# 4x1button_msp430_v5.net
KiCad netlist of a schematic drawn in EAGLE
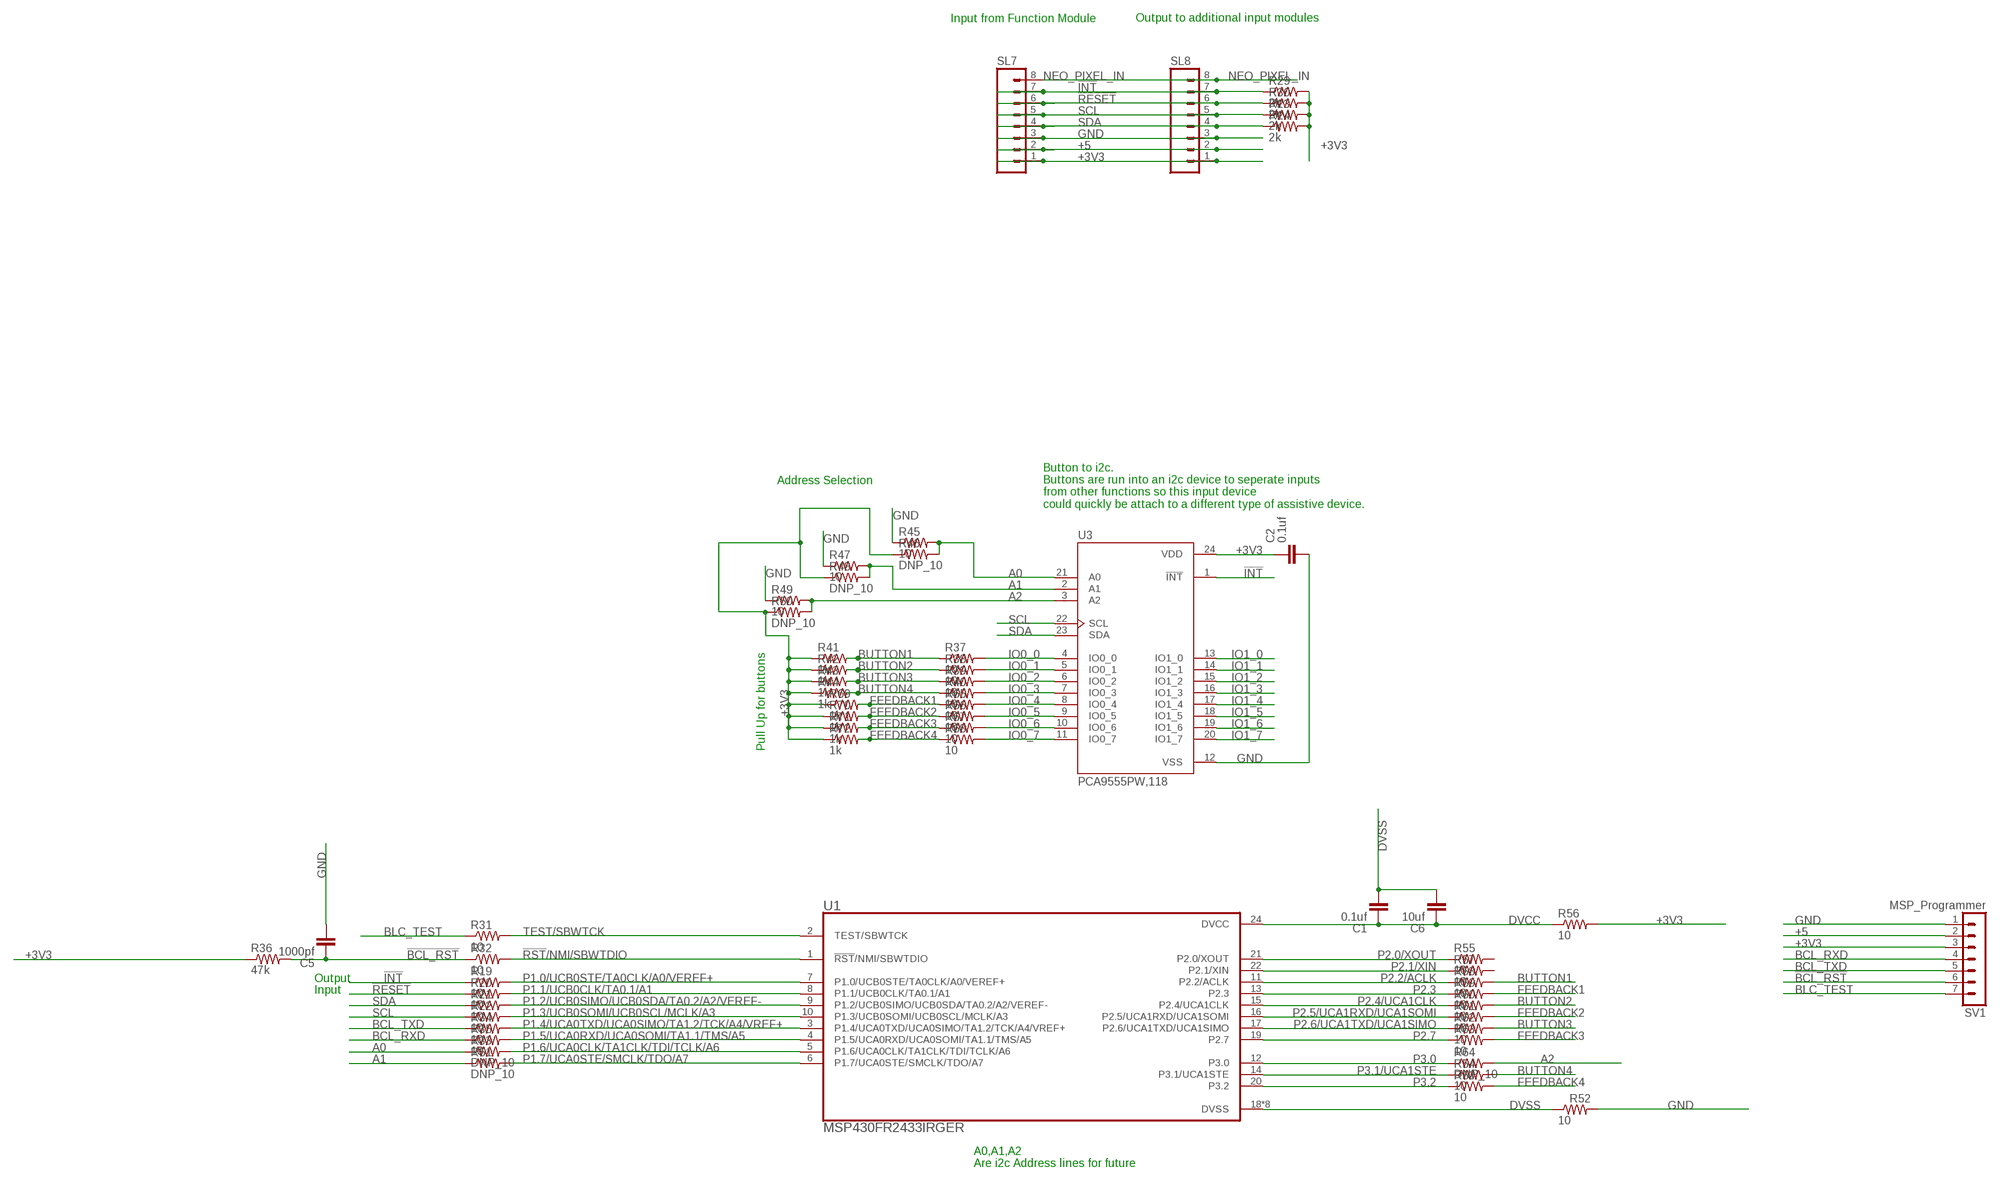
[diagram p0: schematic, sheet 1]
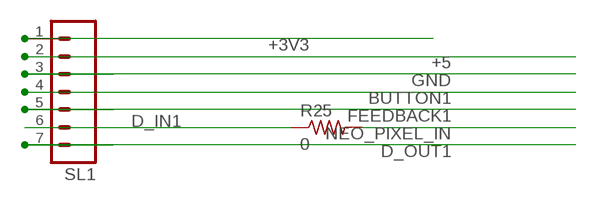
[diagram p1: schematic, sheet 2]
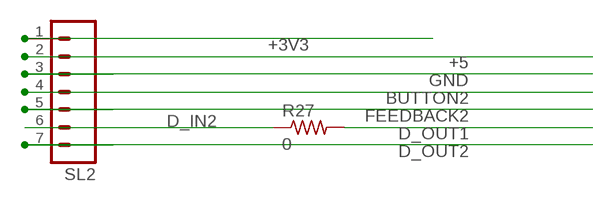
[diagram p2: schematic, sheet 3]
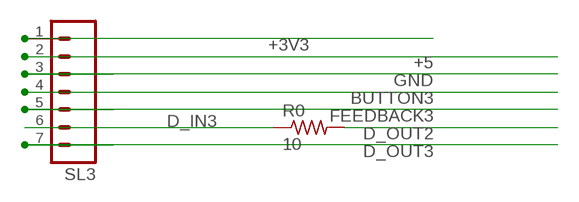
[diagram p3: schematic, sheet 4]
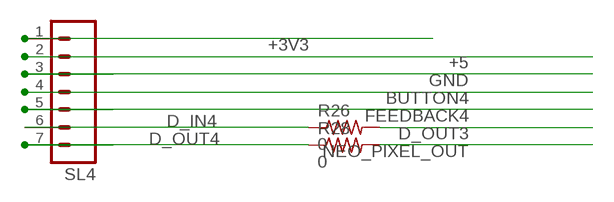
[diagram p4: schematic, sheet 5]
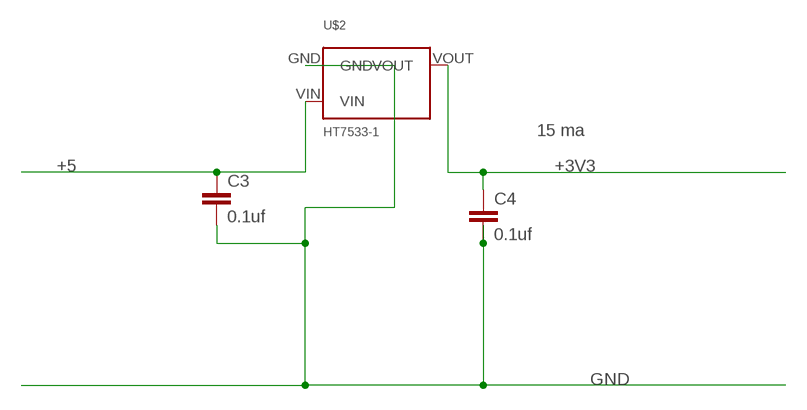
[diagram p5: schematic, sheet 6]

(export (version "E")
  (design (tool "Eeschema 10.0.6"))
  (components
    (comp (ref "R25")
      (value "0")
      (footprint "eagle-import:R0805")
      (libsource (lib "eagle-import") (part "R-US_R0805"))
    )
    (comp (ref "SL1")
      (value "MA07")
      (footprint "eagle-import:07PA")
      (libsource (lib "eagle-import") (part "MA07"))
    )
    (comp (ref "C3")
      (value "0.1uf")
      (footprint "eagle-import:C0805")
      (libsource (lib "eagle-import") (part "C-EUC0805"))
    )
    (comp (ref "C4")
      (value "0.1uf")
      (footprint "eagle-import:C0805")
      (libsource (lib "eagle-import") (part "C-EUC0805"))
    )
    (comp (ref "U$2")
      (value "HT7533-1")
      (footprint "eagle-import:HT7750-1")
      (libsource (lib "eagle-import") (part "HT7550-1"))
    )
    (comp (ref "C1")
      (value "0.1uf")
      (footprint "eagle-import:CAPC2012X110")
      (libsource (lib "eagle-import") (part "CCHIP-0805(2012-METRIC)_"))
    )
    (comp (ref "C2")
      (value "0.1uf")
      (footprint "eagle-import:CAPC2012X110")
      (libsource (lib "eagle-import") (part "CCHIP-0805(2012-METRIC)_"))
    )
    (comp (ref "C5")
      (value "1000pf")
      (footprint "eagle-import:CAPC2012X110")
      (libsource (lib "eagle-import") (part "CCHIP-0805(2012-METRIC)_"))
    )
    (comp (ref "C6")
      (value "10uf")
      (footprint "eagle-import:CAPC2012X110")
      (libsource (lib "eagle-import") (part "CCHIP-0805(2012-METRIC)_"))
    )
    (comp (ref "R19")
      (value "10")
      (footprint "eagle-import:R0805")
      (libsource (lib "eagle-import") (part "R-US_R0805"))
    )
    (comp (ref "R20")
      (value "10")
      (footprint "eagle-import:R0805")
      (libsource (lib "eagle-import") (part "R-US_R0805"))
    )
    (comp (ref "R21")
      (value "10")
      (footprint "eagle-import:R0805")
      (libsource (lib "eagle-import") (part "R-US_R0805"))
    )
    (comp (ref "R22")
      (value "10")
      (footprint "eagle-import:R0805")
      (libsource (lib "eagle-import") (part "R-US_R0805"))
    )
    (comp (ref "R23")
      (value "2k")
      (footprint "eagle-import:R0805")
      (libsource (lib "eagle-import") (part "R-US_R0805"))
    )
    (comp (ref "R24")
      (value "2k")
      (footprint "eagle-import:R0805")
      (libsource (lib "eagle-import") (part "R-US_R0805"))
    )
    (comp (ref "R29")
      (value "2k")
      (footprint "eagle-import:R0805")
      (libsource (lib "eagle-import") (part "R-US_R0805"))
    )
    (comp (ref "R30")
      (value "2k")
      (footprint "eagle-import:R0805")
      (libsource (lib "eagle-import") (part "R-US_R0805"))
    )
    (comp (ref "R31")
      (value "10")
      (footprint "eagle-import:R0805")
      (libsource (lib "eagle-import") (part "R-US_R0805"))
    )
    (comp (ref "R32")
      (value "10")
      (footprint "eagle-import:R0805")
      (libsource (lib "eagle-import") (part "R-US_R0805"))
    )
    (comp (ref "R33")
      (value "DNP_10")
      (footprint "eagle-import:R0805")
      (libsource (lib "eagle-import") (part "R-US_R0805"))
    )
    (comp (ref "R34")
      (value "10")
      (footprint "eagle-import:R0805")
      (libsource (lib "eagle-import") (part "R-US_R0805"))
    )
    (comp (ref "R35")
      (value "10")
      (footprint "eagle-import:R0805")
      (libsource (lib "eagle-import") (part "R-US_R0805"))
    )
    (comp (ref "R36")
      (value "47k")
      (footprint "eagle-import:R0805")
      (libsource (lib "eagle-import") (part "R-US_R0805"))
    )
    (comp (ref "R37")
      (value "10")
      (footprint "eagle-import:R0805")
      (libsource (lib "eagle-import") (part "R-US_R0805"))
    )
    (comp (ref "R38")
      (value "10")
      (footprint "eagle-import:R0805")
      (libsource (lib "eagle-import") (part "R-US_R0805"))
    )
    (comp (ref "R39")
      (value "10")
      (footprint "eagle-import:R0805")
      (libsource (lib "eagle-import") (part "R-US_R0805"))
    )
    (comp (ref "R40")
      (value "10")
      (footprint "eagle-import:R0805")
      (libsource (lib "eagle-import") (part "R-US_R0805"))
    )
    (comp (ref "R41")
      (value "1k")
      (footprint "eagle-import:R0805")
      (libsource (lib "eagle-import") (part "R-US_R0805"))
    )
    (comp (ref "R42")
      (value "1k")
      (footprint "eagle-import:R0805")
      (libsource (lib "eagle-import") (part "R-US_R0805"))
    )
    (comp (ref "R43")
      (value "1k")
      (footprint "eagle-import:R0805")
      (libsource (lib "eagle-import") (part "R-US_R0805"))
    )
    (comp (ref "R44")
      (value "1k")
      (footprint "eagle-import:R0805")
      (libsource (lib "eagle-import") (part "R-US_R0805"))
    )
    (comp (ref "R45")
      (value "10")
      (footprint "eagle-import:R0805")
      (libsource (lib "eagle-import") (part "R-US_R0805"))
    )
    (comp (ref "R46")
      (value "DNP_10")
      (footprint "eagle-import:R0805")
      (libsource (lib "eagle-import") (part "R-US_R0805"))
    )
    (comp (ref "R47")
      (value "10")
      (footprint "eagle-import:R0805")
      (libsource (lib "eagle-import") (part "R-US_R0805"))
    )
    (comp (ref "R48")
      (value "DNP_10")
      (footprint "eagle-import:R0805")
      (libsource (lib "eagle-import") (part "R-US_R0805"))
    )
    (comp (ref "R49")
      (value "10")
      (footprint "eagle-import:R0805")
      (libsource (lib "eagle-import") (part "R-US_R0805"))
    )
    (comp (ref "R50")
      (value "DNP_10")
      (footprint "eagle-import:R0805")
      (libsource (lib "eagle-import") (part "R-US_R0805"))
    )
    (comp (ref "R51")
      (value "DNP_10")
      (footprint "eagle-import:R0805")
      (libsource (lib "eagle-import") (part "R-US_R0805"))
    )
    (comp (ref "R52")
      (value "10")
      (footprint "eagle-import:R0805")
      (libsource (lib "eagle-import") (part "R-US_R0805"))
    )
    (comp (ref "R53")
      (value "10")
      (footprint "eagle-import:R0805")
      (libsource (lib "eagle-import") (part "R-US_R0805"))
    )
    (comp (ref "R54")
      (value "10")
      (footprint "eagle-import:R0805")
      (libsource (lib "eagle-import") (part "R-US_R0805"))
    )
    (comp (ref "R55")
      (value "10")
      (footprint "eagle-import:R0805")
      (libsource (lib "eagle-import") (part "R-US_R0805"))
    )
    (comp (ref "R56")
      (value "10")
      (footprint "eagle-import:R0805")
      (libsource (lib "eagle-import") (part "R-US_R0805"))
    )
    (comp (ref "R57")
      (value "10")
      (footprint "eagle-import:R0805")
      (libsource (lib "eagle-import") (part "R-US_R0805"))
    )
    (comp (ref "R58")
      (value "10")
      (footprint "eagle-import:R0805")
      (libsource (lib "eagle-import") (part "R-US_R0805"))
    )
    (comp (ref "R59")
      (value "10")
      (footprint "eagle-import:R0805")
      (libsource (lib "eagle-import") (part "R-US_R0805"))
    )
    (comp (ref "R60")
      (value "10")
      (footprint "eagle-import:R0805")
      (libsource (lib "eagle-import") (part "R-US_R0805"))
    )
    (comp (ref "R61")
      (value "10")
      (footprint "eagle-import:R0805")
      (libsource (lib "eagle-import") (part "R-US_R0805"))
    )
    (comp (ref "R62")
      (value "10")
      (footprint "eagle-import:R0805")
      (libsource (lib "eagle-import") (part "R-US_R0805"))
    )
    (comp (ref "R63")
      (value "10")
      (footprint "eagle-import:R0805")
      (libsource (lib "eagle-import") (part "R-US_R0805"))
    )
    (comp (ref "R64")
      (value "DNP_10")
      (footprint "eagle-import:R0805")
      (libsource (lib "eagle-import") (part "R-US_R0805"))
    )
    (comp (ref "R65")
      (value "10")
      (footprint "eagle-import:R0805")
      (libsource (lib "eagle-import") (part "R-US_R0805"))
    )
    (comp (ref "R66")
      (value "10")
      (footprint "eagle-import:R0805")
      (libsource (lib "eagle-import") (part "R-US_R0805"))
    )
    (comp (ref "R67")
      (value "10")
      (footprint "eagle-import:R0805")
      (libsource (lib "eagle-import") (part "R-US_R0805"))
    )
    (comp (ref "R68")
      (value "10")
      (footprint "eagle-import:R0805")
      (libsource (lib "eagle-import") (part "R-US_R0805"))
    )
    (comp (ref "R69")
      (value "1k")
      (footprint "eagle-import:R0805")
      (libsource (lib "eagle-import") (part "R-US_R0805"))
    )
    (comp (ref "R70")
      (value "1k")
      (footprint "eagle-import:R0805")
      (libsource (lib "eagle-import") (part "R-US_R0805"))
    )
    (comp (ref "R71")
      (value "1k")
      (footprint "eagle-import:R0805")
      (libsource (lib "eagle-import") (part "R-US_R0805"))
    )
    (comp (ref "R72")
      (value "1k")
      (footprint "eagle-import:R0805")
      (libsource (lib "eagle-import") (part "R-US_R0805"))
    )
    (comp (ref "SL7")
      (value "MA08")
      (footprint "eagle-import:08PA")
      (libsource (lib "eagle-import") (part "MA08"))
    )
    (comp (ref "SL8")
      (value "MA08")
      (footprint "eagle-import:08PA")
      (libsource (lib "eagle-import") (part "MA08"))
    )
    (comp (ref "SV1")
      (value "MSP_Programmer")
      (footprint "eagle-import:MA07-1")
      (libsource (lib "eagle-import") (part "MA07-1"))
    )
    (comp (ref "U1")
      (value "MSP430FR2433IRGER")
      (footprint "eagle-import:QFN50P400X400X100-25N")
      (fields (field (name "MANUFACTURER") "Texas Instruments"))
      (libsource (lib "eagle-import") (part "MSP430FR2433IRGER"))
    )
    (comp (ref "U3")
      (value "PCA9555PW,118")
      (footprint "eagle-import:SOP65P640X110-24N")
      (fields (field (name "MANUFACTURER") "NXP"))
      (libsource (lib "eagle-import") (part "PCA9555PW,118"))
    )
    (comp (ref "R27")
      (value "0")
      (footprint "eagle-import:R0805")
      (libsource (lib "eagle-import") (part "R-US_R0805"))
    )
    (comp (ref "SL2")
      (value "MA07")
      (footprint "eagle-import:07PA")
      (libsource (lib "eagle-import") (part "MA07"))
    )
    (comp (ref "R26")
      (value "0")
      (footprint "eagle-import:R0805")
      (libsource (lib "eagle-import") (part "R-US_R0805"))
    )
    (comp (ref "R28")
      (value "0")
      (footprint "eagle-import:R0805")
      (libsource (lib "eagle-import") (part "R-US_R0805"))
    )
    (comp (ref "SL4")
      (value "MA07")
      (footprint "eagle-import:07PA")
      (libsource (lib "eagle-import") (part "MA07"))
    )
    (comp (ref "R0")
      (value "10")
      (footprint "eagle-import:R0805")
      (libsource (lib "eagle-import") (part "R-US_R0805"))
    )
    (comp (ref "SL3")
      (value "MA07")
      (footprint "eagle-import:07PA")
      (libsource (lib "eagle-import") (part "MA07"))
    )
  )
  (nets
    (net (code "1") (name "+3V3") (class "Default")
      (node (ref "C2") (pin "1") (pinfunction "1_1") (pintype "passive"))
      (node (ref "C4") (pin "1") (pinfunction "1_1") (pintype "passive"))
      (node (ref "R23") (pin "2") (pinfunction "2_2") (pintype "passive"))
      (node (ref "R24") (pin "2") (pinfunction "2_2") (pintype "passive"))
      (node (ref "R29") (pin "2") (pinfunction "2_2") (pintype "passive"))
      (node (ref "R30") (pin "2") (pinfunction "2_2") (pintype "passive"))
      (node (ref "R36") (pin "1") (pinfunction "1_1") (pintype "passive"))
      (node (ref "R41") (pin "1") (pinfunction "1_1") (pintype "passive"))
      (node (ref "R42") (pin "1") (pinfunction "1_1") (pintype "passive"))
      (node (ref "R43") (pin "1") (pinfunction "1_1") (pintype "passive"))
      (node (ref "R44") (pin "1") (pinfunction "1_1") (pintype "passive"))
      (node (ref "R46") (pin "1") (pinfunction "1_1") (pintype "passive"))
      (node (ref "R48") (pin "1") (pinfunction "1_1") (pintype "passive"))
      (node (ref "R50") (pin "1") (pinfunction "1_1") (pintype "passive"))
      (node (ref "R56") (pin "2") (pinfunction "2_2") (pintype "passive"))
      (node (ref "R69") (pin "1") (pinfunction "1_1") (pintype "passive"))
      (node (ref "R70") (pin "1") (pinfunction "1_1") (pintype "passive"))
      (node (ref "R71") (pin "1") (pinfunction "1_1") (pintype "passive"))
      (node (ref "R72") (pin "1") (pinfunction "1_1") (pintype "passive"))
      (node (ref "SL1") (pin "1") (pinfunction "1_1") (pintype "passive"))
      (node (ref "SL2") (pin "1") (pinfunction "1_1") (pintype "passive"))
      (node (ref "SL3") (pin "1") (pinfunction "1_1") (pintype "passive"))
      (node (ref "SL4") (pin "1") (pinfunction "1_1") (pintype "passive"))
      (node (ref "SL7") (pin "1") (pinfunction "1_1") (pintype "passive"))
      (node (ref "SL8") (pin "1") (pinfunction "1_1") (pintype "passive"))
      (node (ref "SV1") (pin "3") (pinfunction "3_3") (pintype "passive"))
      (node (ref "U$2") (pin "VOUT") (pinfunction "VOUT_VOUT") (pintype "power_in"))
      (node (ref "U3") (pin "24") (pinfunction "VDD_24") (pintype "power_in"))
    )
    (net (code "2") (name "+5") (class "Default")
      (node (ref "C3") (pin "1") (pinfunction "1_1") (pintype "passive"))
      (node (ref "SL1") (pin "2") (pinfunction "2_2") (pintype "passive"))
      (node (ref "SL2") (pin "2") (pinfunction "2_2") (pintype "passive"))
      (node (ref "SL3") (pin "2") (pinfunction "2_2") (pintype "passive"))
      (node (ref "SL4") (pin "2") (pinfunction "2_2") (pintype "passive"))
      (node (ref "SL7") (pin "2") (pinfunction "2_2") (pintype "passive"))
      (node (ref "SL8") (pin "2") (pinfunction "2_2") (pintype "passive"))
      (node (ref "SV1") (pin "2") (pinfunction "2_2") (pintype "passive"))
      (node (ref "U$2") (pin "VIN") (pinfunction "VIN_VIN") (pintype "power_in"))
    )
    (net (code "3") (name "A0") (class "Default")
      (node (ref "R33") (pin "1") (pinfunction "1_1") (pintype "passive"))
      (node (ref "R45") (pin "2") (pinfunction "2_2") (pintype "passive"))
      (node (ref "R46") (pin "2") (pinfunction "2_2") (pintype "passive"))
      (node (ref "U3") (pin "21") (pinfunction "A0_21") (pintype "input"))
    )
    (net (code "4") (name "A1") (class "Default")
      (node (ref "R47") (pin "2") (pinfunction "2_2") (pintype "passive"))
      (node (ref "R48") (pin "2") (pinfunction "2_2") (pintype "passive"))
      (node (ref "R51") (pin "1") (pinfunction "1_1") (pintype "passive"))
      (node (ref "U3") (pin "2") (pinfunction "A1_2") (pintype "input"))
    )
    (net (code "5") (name "A2") (class "Default")
      (node (ref "R49") (pin "2") (pinfunction "2_2") (pintype "passive"))
      (node (ref "R50") (pin "2") (pinfunction "2_2") (pintype "passive"))
      (node (ref "R64") (pin "2") (pinfunction "2_2") (pintype "passive"))
      (node (ref "U3") (pin "3") (pinfunction "A2_3") (pintype "input"))
    )
    (net (code "6") (name "BCL_RXD") (class "Default")
      (node (ref "R35") (pin "1") (pinfunction "1_1") (pintype "passive"))
      (node (ref "SV1") (pin "4") (pinfunction "4_4") (pintype "passive"))
    )
    (net (code "7") (name "BCL_TXD") (class "Default")
      (node (ref "R34") (pin "1") (pinfunction "1_1") (pintype "passive"))
      (node (ref "SV1") (pin "5") (pinfunction "5_5") (pintype "passive"))
    )
    (net (code "8") (name "BLC_TEST") (class "Default")
      (node (ref "R31") (pin "1") (pinfunction "1_1") (pintype "passive"))
      (node (ref "SV1") (pin "7") (pinfunction "7_7") (pintype "passive"))
    )
    (net (code "9") (name "BUTTON1") (class "Default")
      (node (ref "R37") (pin "1") (pinfunction "1_1") (pintype "passive"))
      (node (ref "R41") (pin "2") (pinfunction "2_2") (pintype "passive"))
      (node (ref "R58") (pin "2") (pinfunction "2_2") (pintype "passive"))
      (node (ref "SL1") (pin "4") (pinfunction "4_4") (pintype "passive"))
    )
    (net (code "10") (name "BUTTON2") (class "Default")
      (node (ref "R38") (pin "1") (pinfunction "1_1") (pintype "passive"))
      (node (ref "R42") (pin "2") (pinfunction "2_2") (pintype "passive"))
      (node (ref "R60") (pin "2") (pinfunction "2_2") (pintype "passive"))
      (node (ref "SL2") (pin "4") (pinfunction "4_4") (pintype "passive"))
    )
    (net (code "11") (name "BUTTON3") (class "Default")
      (node (ref "R39") (pin "1") (pinfunction "1_1") (pintype "passive"))
      (node (ref "R43") (pin "2") (pinfunction "2_2") (pintype "passive"))
      (node (ref "R62") (pin "2") (pinfunction "2_2") (pintype "passive"))
      (node (ref "SL3") (pin "4") (pinfunction "4_4") (pintype "passive"))
    )
    (net (code "12") (name "BUTTON4") (class "Default")
      (node (ref "R40") (pin "1") (pinfunction "1_1") (pintype "passive"))
      (node (ref "R44") (pin "2") (pinfunction "2_2") (pintype "passive"))
      (node (ref "R54") (pin "2") (pinfunction "2_2") (pintype "passive"))
      (node (ref "SL4") (pin "4") (pinfunction "4_4") (pintype "passive"))
    )
    (net (code "13") (name "DVCC") (class "Default")
      (node (ref "C1") (pin "1") (pinfunction "1_1") (pintype "passive"))
      (node (ref "C6") (pin "1") (pinfunction "1_1") (pintype "passive"))
      (node (ref "R56") (pin "1") (pinfunction "1_1") (pintype "passive"))
      (node (ref "U1") (pin "24") (pinfunction "DVCC_24") (pintype "power_in"))
    )
    (net (code "14") (name "DVSS") (class "Default")
      (node (ref "C1") (pin "2") (pinfunction "2_2") (pintype "passive"))
      (node (ref "C6") (pin "2") (pinfunction "2_2") (pintype "passive"))
      (node (ref "R52") (pin "1") (pinfunction "1_1") (pintype "passive"))
      (node (ref "U1") (pin "18") (pinfunction "DVSS_18") (pintype "power_in"))
      (node (ref "U1") (pin "23") (pinfunction "DVSS_23") (pintype "power_in"))
      (node (ref "U1") (pin "25") (pinfunction "DVSS_25") (pintype "power_in"))
      (node (ref "U1") (pin "26") (pinfunction "DVSS_26") (pintype "power_in"))
      (node (ref "U1") (pin "27") (pinfunction "DVSS_27") (pintype "power_in"))
      (node (ref "U1") (pin "28") (pinfunction "DVSS_28") (pintype "power_in"))
      (node (ref "U1") (pin "29") (pinfunction "DVSS_29") (pintype "power_in"))
      (node (ref "U1") (pin "30") (pinfunction "DVSS_30") (pintype "power_in"))
    )
    (net (code "15") (name "D_IN1") (class "Default")
      (node (ref "R25") (pin "1") (pinfunction "1_1") (pintype "passive"))
      (node (ref "SL1") (pin "6") (pinfunction "6_6") (pintype "passive"))
    )
    (net (code "16") (name "D_IN2") (class "Default")
      (node (ref "R27") (pin "1") (pinfunction "1_1") (pintype "passive"))
      (node (ref "SL2") (pin "6") (pinfunction "6_6") (pintype "passive"))
    )
    (net (code "17") (name "D_IN3") (class "Default")
      (node (ref "R0") (pin "1") (pinfunction "1_1") (pintype "passive"))
      (node (ref "SL3") (pin "6") (pinfunction "6_6") (pintype "passive"))
    )
    (net (code "18") (name "D_IN4") (class "Default")
      (node (ref "R26") (pin "1") (pinfunction "1_1") (pintype "passive"))
      (node (ref "SL4") (pin "6") (pinfunction "6_6") (pintype "passive"))
    )
    (net (code "19") (name "D_OUT1") (class "Default")
      (node (ref "R27") (pin "2") (pinfunction "2_2") (pintype "passive"))
      (node (ref "SL1") (pin "7") (pinfunction "7_7") (pintype "passive"))
    )
    (net (code "20") (name "D_OUT2") (class "Default")
      (node (ref "R0") (pin "2") (pinfunction "2_2") (pintype "passive"))
      (node (ref "SL2") (pin "7") (pinfunction "7_7") (pintype "passive"))
    )
    (net (code "21") (name "D_OUT3") (class "Default")
      (node (ref "R26") (pin "2") (pinfunction "2_2") (pintype "passive"))
      (node (ref "SL3") (pin "7") (pinfunction "7_7") (pintype "passive"))
    )
    (net (code "22") (name "D_OUT4") (class "Default")
      (node (ref "R28") (pin "1") (pinfunction "1_1") (pintype "passive"))
      (node (ref "SL4") (pin "7") (pinfunction "7_7") (pintype "passive"))
    )
    (net (code "23") (name "FEEDBACK1") (class "Default")
      (node (ref "R59") (pin "2") (pinfunction "2_2") (pintype "passive"))
      (node (ref "R65") (pin "1") (pinfunction "1_1") (pintype "passive"))
      (node (ref "R69") (pin "2") (pinfunction "2_2") (pintype "passive"))
      (node (ref "SL1") (pin "5") (pinfunction "5_5") (pintype "passive"))
    )
    (net (code "24") (name "FEEDBACK2") (class "Default")
      (node (ref "R61") (pin "2") (pinfunction "2_2") (pintype "passive"))
      (node (ref "R66") (pin "1") (pinfunction "1_1") (pintype "passive"))
      (node (ref "R70") (pin "2") (pinfunction "2_2") (pintype "passive"))
      (node (ref "SL2") (pin "5") (pinfunction "5_5") (pintype "passive"))
    )
    (net (code "25") (name "FEEDBACK3") (class "Default")
      (node (ref "R63") (pin "2") (pinfunction "2_2") (pintype "passive"))
      (node (ref "R67") (pin "1") (pinfunction "1_1") (pintype "passive"))
      (node (ref "R71") (pin "2") (pinfunction "2_2") (pintype "passive"))
      (node (ref "SL3") (pin "5") (pinfunction "5_5") (pintype "passive"))
    )
    (net (code "26") (name "FEEDBACK4") (class "Default")
      (node (ref "R53") (pin "2") (pinfunction "2_2") (pintype "passive"))
      (node (ref "R68") (pin "1") (pinfunction "1_1") (pintype "passive"))
      (node (ref "R72") (pin "2") (pinfunction "2_2") (pintype "passive"))
      (node (ref "SL4") (pin "5") (pinfunction "5_5") (pintype "passive"))
    )
    (net (code "27") (name "GND") (class "Default")
      (node (ref "C2") (pin "2") (pinfunction "2_2") (pintype "passive"))
      (node (ref "C3") (pin "2") (pinfunction "2_2") (pintype "passive"))
      (node (ref "C4") (pin "2") (pinfunction "2_2") (pintype "passive"))
      (node (ref "C5") (pin "2") (pinfunction "2_2") (pintype "passive"))
      (node (ref "R45") (pin "1") (pinfunction "1_1") (pintype "passive"))
      (node (ref "R47") (pin "1") (pinfunction "1_1") (pintype "passive"))
      (node (ref "R49") (pin "1") (pinfunction "1_1") (pintype "passive"))
      (node (ref "R52") (pin "2") (pinfunction "2_2") (pintype "passive"))
      (node (ref "SL1") (pin "3") (pinfunction "3_3") (pintype "passive"))
      (node (ref "SL2") (pin "3") (pinfunction "3_3") (pintype "passive"))
      (node (ref "SL3") (pin "3") (pinfunction "3_3") (pintype "passive"))
      (node (ref "SL4") (pin "3") (pinfunction "3_3") (pintype "passive"))
      (node (ref "SL7") (pin "3") (pinfunction "3_3") (pintype "passive"))
      (node (ref "SL8") (pin "3") (pinfunction "3_3") (pintype "passive"))
      (node (ref "SV1") (pin "1") (pinfunction "1_1") (pintype "passive"))
      (node (ref "U$2") (pin "GND") (pinfunction "GND_GND") (pintype "power_in"))
      (node (ref "U3") (pin "12") (pinfunction "VSS_12") (pintype "power_in"))
    )
    (net (code "28") (name "IO0_0") (class "Default")
      (node (ref "R37") (pin "2") (pinfunction "2_2") (pintype "passive"))
      (node (ref "U3") (pin "4") (pinfunction "IO0_0_4") (pintype "bidirectional"))
    )
    (net (code "29") (name "IO0_1") (class "Default")
      (node (ref "R38") (pin "2") (pinfunction "2_2") (pintype "passive"))
      (node (ref "U3") (pin "5") (pinfunction "IO0_1_5") (pintype "bidirectional"))
    )
    (net (code "30") (name "IO0_2") (class "Default")
      (node (ref "R39") (pin "2") (pinfunction "2_2") (pintype "passive"))
      (node (ref "U3") (pin "6") (pinfunction "IO0_2_6") (pintype "bidirectional"))
    )
    (net (code "31") (name "IO0_3") (class "Default")
      (node (ref "R40") (pin "2") (pinfunction "2_2") (pintype "passive"))
      (node (ref "U3") (pin "7") (pinfunction "IO0_3_7") (pintype "bidirectional"))
    )
    (net (code "32") (name "IO0_4") (class "Default")
      (node (ref "R65") (pin "2") (pinfunction "2_2") (pintype "passive"))
      (node (ref "U3") (pin "8") (pinfunction "IO0_4_8") (pintype "bidirectional"))
    )
    (net (code "33") (name "IO0_5") (class "Default")
      (node (ref "R66") (pin "2") (pinfunction "2_2") (pintype "passive"))
      (node (ref "U3") (pin "9") (pinfunction "IO0_5_9") (pintype "bidirectional"))
    )
    (net (code "34") (name "IO0_6") (class "Default")
      (node (ref "R67") (pin "2") (pinfunction "2_2") (pintype "passive"))
      (node (ref "U3") (pin "10") (pinfunction "IO0_6_10") (pintype "bidirectional"))
    )
    (net (code "35") (name "IO0_7") (class "Default")
      (node (ref "R68") (pin "2") (pinfunction "2_2") (pintype "passive"))
      (node (ref "U3") (pin "11") (pinfunction "IO0_7_11") (pintype "bidirectional"))
    )
    (net (code "36") (name "IO1_0") (class "Default")
      (node (ref "U3") (pin "13") (pinfunction "IO1_0_13") (pintype "bidirectional"))
    )
    (net (code "37") (name "IO1_1") (class "Default")
      (node (ref "U3") (pin "14") (pinfunction "IO1_1_14") (pintype "bidirectional"))
    )
    (net (code "38") (name "IO1_2") (class "Default")
      (node (ref "U3") (pin "15") (pinfunction "IO1_2_15") (pintype "bidirectional"))
    )
    (net (code "39") (name "IO1_3") (class "Default")
      (node (ref "U3") (pin "16") (pinfunction "IO1_3_16") (pintype "bidirectional"))
    )
    (net (code "40") (name "IO1_4") (class "Default")
      (node (ref "U3") (pin "17") (pinfunction "IO1_4_17") (pintype "bidirectional"))
    )
    (net (code "41") (name "IO1_5") (class "Default")
      (node (ref "U3") (pin "18") (pinfunction "IO1_5_18") (pintype "bidirectional"))
    )
    (net (code "42") (name "IO1_6") (class "Default")
      (node (ref "U3") (pin "19") (pinfunction "IO1_6_19") (pintype "bidirectional"))
    )
    (net (code "43") (name "IO1_7") (class "Default")
      (node (ref "U3") (pin "20") (pinfunction "IO1_7_20") (pintype "bidirectional"))
    )
    (net (code "44") (name "NEO_PIXEL_IN") (class "Default")
      (node (ref "R25") (pin "2") (pinfunction "2_2") (pintype "passive"))
      (node (ref "SL7") (pin "8") (pinfunction "8_8") (pintype "passive"))
      (node (ref "SL8") (pin "8") (pinfunction "8_8") (pintype "passive"))
    )
    (net (code "45") (name "NEO_PIXEL_OUT") (class "Default")
      (node (ref "R28") (pin "2") (pinfunction "2_2") (pintype "passive"))
    )
    (net (code "46") (name "P1.0{slash}UCB0STE{slash}TA0CLK{slash}A0{slash}VEREF+") (class "Default")
      (node (ref "R19") (pin "2") (pinfunction "2_2") (pintype "passive"))
      (node (ref "U1") (pin "7") (pinfunction "P1.0/UCB0STE/TA0CLK/A0/VEREF+_7") (pintype "bidirectional"))
    )
    (net (code "47") (name "P1.1{slash}UCB0CLK{slash}TA0.1{slash}A1") (class "Default")
      (node (ref "R20") (pin "2") (pinfunction "2_2") (pintype "passive"))
      (node (ref "U1") (pin "8") (pinfunction "P1.1/UCB0CLK/TA0.1/A1_8") (pintype "bidirectional"))
    )
    (net (code "48") (name "P1.2{slash}UCB0SIMO{slash}UCB0SDA{slash}TA0.2{slash}A2{slash}VEREF-") (class "Default")
      (node (ref "R21") (pin "2") (pinfunction "2_2") (pintype "passive"))
      (node (ref "U1") (pin "9") (pinfunction "P1.2/UCB0SIMO/UCB0SDA/TA0.2/A2/VEREF-_9") (pintype "bidirectional"))
    )
    (net (code "49") (name "P1.3{slash}UCB0SOMI{slash}UCB0SCL{slash}MCLK{slash}A3") (class "Default")
      (node (ref "R22") (pin "2") (pinfunction "2_2") (pintype "passive"))
      (node (ref "U1") (pin "10") (pinfunction "P1.3/UCB0SOMI/UCB0SCL/MCLK/A3_10") (pintype "bidirectional"))
    )
    (net (code "50") (name "P1.4{slash}UCA0TXD{slash}UCA0SIMO{slash}TA1.2{slash}TCK{slash}A4{slash}VREF+") (class "Default")
      (node (ref "R34") (pin "2") (pinfunction "2_2") (pintype "passive"))
      (node (ref "U1") (pin "3") (pinfunction "P1.4/UCA0TXD/UCA0SIMO/TA1.2/TCK/A4/VREF+_3") (pintype "bidirectional"))
    )
    (net (code "51") (name "P1.5{slash}UCA0RXD{slash}UCA0SOMI{slash}TA1.1{slash}TMS{slash}A5") (class "Default")
      (node (ref "R35") (pin "2") (pinfunction "2_2") (pintype "passive"))
      (node (ref "U1") (pin "4") (pinfunction "P1.5/UCA0RXD/UCA0SOMI/TA1.1/TMS/A5_4") (pintype "bidirectional"))
    )
    (net (code "52") (name "P1.6{slash}UCA0CLK{slash}TA1CLK{slash}TDI{slash}TCLK{slash}A6") (class "Default")
      (node (ref "R33") (pin "2") (pinfunction "2_2") (pintype "passive"))
      (node (ref "U1") (pin "5") (pinfunction "P1.6/UCA0CLK/TA1CLK/TDI/TCLK/A6_5") (pintype "bidirectional"))
    )
    (net (code "53") (name "P1.7{slash}UCA0STE{slash}SMCLK{slash}TDO{slash}A7") (class "Default")
      (node (ref "R51") (pin "2") (pinfunction "2_2") (pintype "passive"))
      (node (ref "U1") (pin "6") (pinfunction "P1.7/UCA0STE/SMCLK/TDO/A7_6") (pintype "bidirectional"))
    )
    (net (code "54") (name "P2.0{slash}XOUT") (class "Default")
      (node (ref "R55") (pin "1") (pinfunction "1_1") (pintype "passive"))
      (node (ref "U1") (pin "21") (pinfunction "P2.0/XOUT_21") (pintype "bidirectional"))
    )
    (net (code "55") (name "P2.1{slash}XIN") (class "Default")
      (node (ref "R57") (pin "1") (pinfunction "1_1") (pintype "passive"))
      (node (ref "U1") (pin "22") (pinfunction "P2.1/XIN_22") (pintype "bidirectional"))
    )
    (net (code "56") (name "P2.2{slash}ACLK") (class "Default")
      (node (ref "R58") (pin "1") (pinfunction "1_1") (pintype "passive"))
      (node (ref "U1") (pin "11") (pinfunction "P2.2/ACLK_11") (pintype "bidirectional"))
    )
    (net (code "57") (name "P2.3") (class "Default")
      (node (ref "R59") (pin "1") (pinfunction "1_1") (pintype "passive"))
      (node (ref "U1") (pin "13") (pinfunction "P2.3_13") (pintype "bidirectional"))
    )
    (net (code "58") (name "P2.4{slash}UCA1CLK") (class "Default")
      (node (ref "R60") (pin "1") (pinfunction "1_1") (pintype "passive"))
      (node (ref "U1") (pin "15") (pinfunction "P2.4/UCA1CLK_15") (pintype "bidirectional"))
    )
    (net (code "59") (name "P2.5{slash}UCA1RXD{slash}UCA1SOMI") (class "Default")
      (node (ref "R61") (pin "1") (pinfunction "1_1") (pintype "passive"))
      (node (ref "U1") (pin "16") (pinfunction "P2.5/UCA1RXD/UCA1SOMI_16") (pintype "bidirectional"))
    )
    (net (code "60") (name "P2.6{slash}UCA1TXD{slash}UCA1SIMO") (class "Default")
      (node (ref "R62") (pin "1") (pinfunction "1_1") (pintype "passive"))
      (node (ref "U1") (pin "17") (pinfunction "P2.6/UCA1TXD/UCA1SIMO_17") (pintype "bidirectional"))
    )
    (net (code "61") (name "P2.7") (class "Default")
      (node (ref "R63") (pin "1") (pinfunction "1_1") (pintype "passive"))
      (node (ref "U1") (pin "19") (pinfunction "P2.7_19") (pintype "bidirectional"))
    )
    (net (code "62") (name "P3.0") (class "Default")
      (node (ref "R64") (pin "1") (pinfunction "1_1") (pintype "passive"))
      (node (ref "U1") (pin "12") (pinfunction "P3.0_12") (pintype "bidirectional"))
    )
    (net (code "63") (name "P3.1{slash}UCA1STE") (class "Default")
      (node (ref "R54") (pin "1") (pinfunction "1_1") (pintype "passive"))
      (node (ref "U1") (pin "14") (pinfunction "P3.1/UCA1STE_14") (pintype "bidirectional"))
    )
    (net (code "64") (name "P3.2") (class "Default")
      (node (ref "R53") (pin "1") (pinfunction "1_1") (pintype "passive"))
      (node (ref "U1") (pin "20") (pinfunction "P3.2_20") (pintype "bidirectional"))
    )
    (net (code "65") (name "SCL") (class "Default")
      (node (ref "R22") (pin "1") (pinfunction "1_1") (pintype "passive"))
      (node (ref "R23") (pin "1") (pinfunction "1_1") (pintype "passive"))
      (node (ref "SL7") (pin "5") (pinfunction "5_5") (pintype "passive"))
      (node (ref "SL8") (pin "5") (pinfunction "5_5") (pintype "passive"))
      (node (ref "U3") (pin "22") (pinfunction "SCL_22") (pintype "input"))
    )
    (net (code "66") (name "SDA") (class "Default")
      (node (ref "R21") (pin "1") (pinfunction "1_1") (pintype "passive"))
      (node (ref "R24") (pin "1") (pinfunction "1_1") (pintype "passive"))
      (node (ref "SL7") (pin "4") (pinfunction "4_4") (pintype "passive"))
      (node (ref "SL8") (pin "4") (pinfunction "4_4") (pintype "passive"))
      (node (ref "U3") (pin "23") (pinfunction "SDA_23") (pintype "bidirectional"))
    )
    (net (code "67") (name "TEST{slash}SBWTCK") (class "Default")
      (node (ref "R31") (pin "2") (pinfunction "2_2") (pintype "passive"))
      (node (ref "U1") (pin "2") (pinfunction "TEST/SBWTCK_2") (pintype "input"))
    )
    (net (code "68") (name "unconnected-(R55-Pad2)") (class "Default")
      (node (ref "R55") (pin "2") (pinfunction "2_2") (pintype "passive"))
    )
    (net (code "69") (name "unconnected-(R57-Pad2)") (class "Default")
      (node (ref "R57") (pin "2") (pinfunction "2_2") (pintype "passive"))
    )
    (net (code "70") (name "~{BCL_RST}") (class "Default")
      (node (ref "C5") (pin "1") (pinfunction "1_1") (pintype "passive"))
      (node (ref "R32") (pin "1") (pinfunction "1_1") (pintype "passive"))
      (node (ref "R36") (pin "2") (pinfunction "2_2") (pintype "passive"))
      (node (ref "SV1") (pin "6") (pinfunction "6_6") (pintype "passive"))
    )
    (net (code "71") (name "~{INT}") (class "Default")
      (node (ref "R19") (pin "1") (pinfunction "1_1") (pintype "passive"))
      (node (ref "R29") (pin "1") (pinfunction "1_1") (pintype "passive"))
      (node (ref "SL7") (pin "7") (pinfunction "7_7") (pintype "passive"))
      (node (ref "SL8") (pin "7") (pinfunction "7_7") (pintype "passive"))
      (node (ref "U3") (pin "1") (pinfunction "~{INT}_1") (pintype "output"))
    )
    (net (code "72") (name "~{RESET}") (class "Default")
      (node (ref "R20") (pin "1") (pinfunction "1_1") (pintype "passive"))
      (node (ref "R30") (pin "1") (pinfunction "1_1") (pintype "passive"))
      (node (ref "SL7") (pin "6") (pinfunction "6_6") (pintype "passive"))
      (node (ref "SL8") (pin "6") (pinfunction "6_6") (pintype "passive"))
    )
    (net (code "73") (name "~{RST}{slash}NMI{slash}SBWTDIO") (class "Default")
      (node (ref "R32") (pin "2") (pinfunction "2_2") (pintype "passive"))
      (node (ref "U1") (pin "1") (pinfunction "~{RST}/NMI/SBWTDIO_1") (pintype "bidirectional"))
    )
  )
)
